# DRV8301.net
KiCad netlist of a schematic drawn in Altium Designer
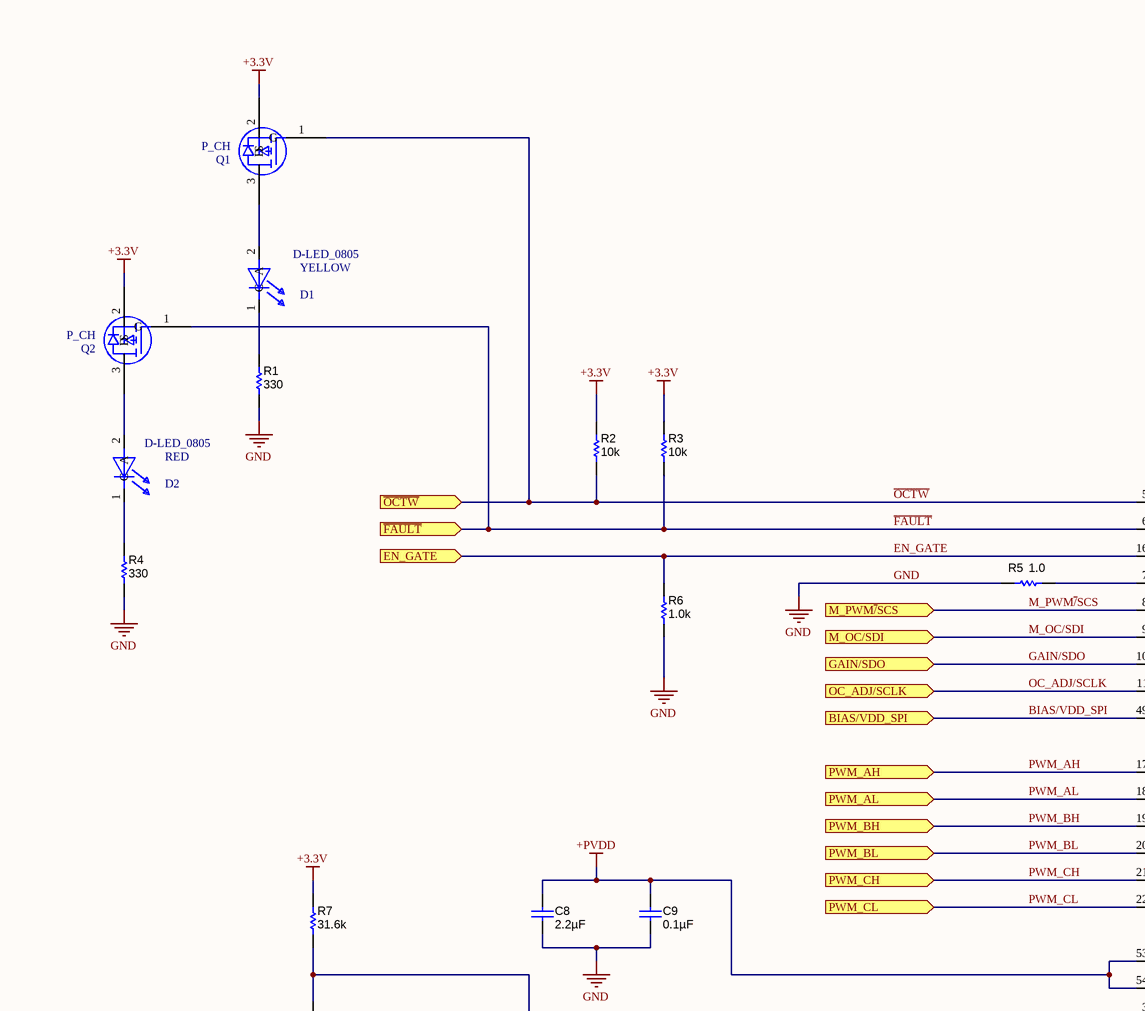
[diagram p0: DRV8301.SchDoc, top left]
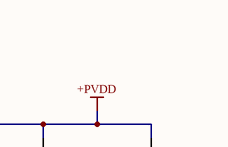
[diagram p1: DRV8301.SchDoc, top right]
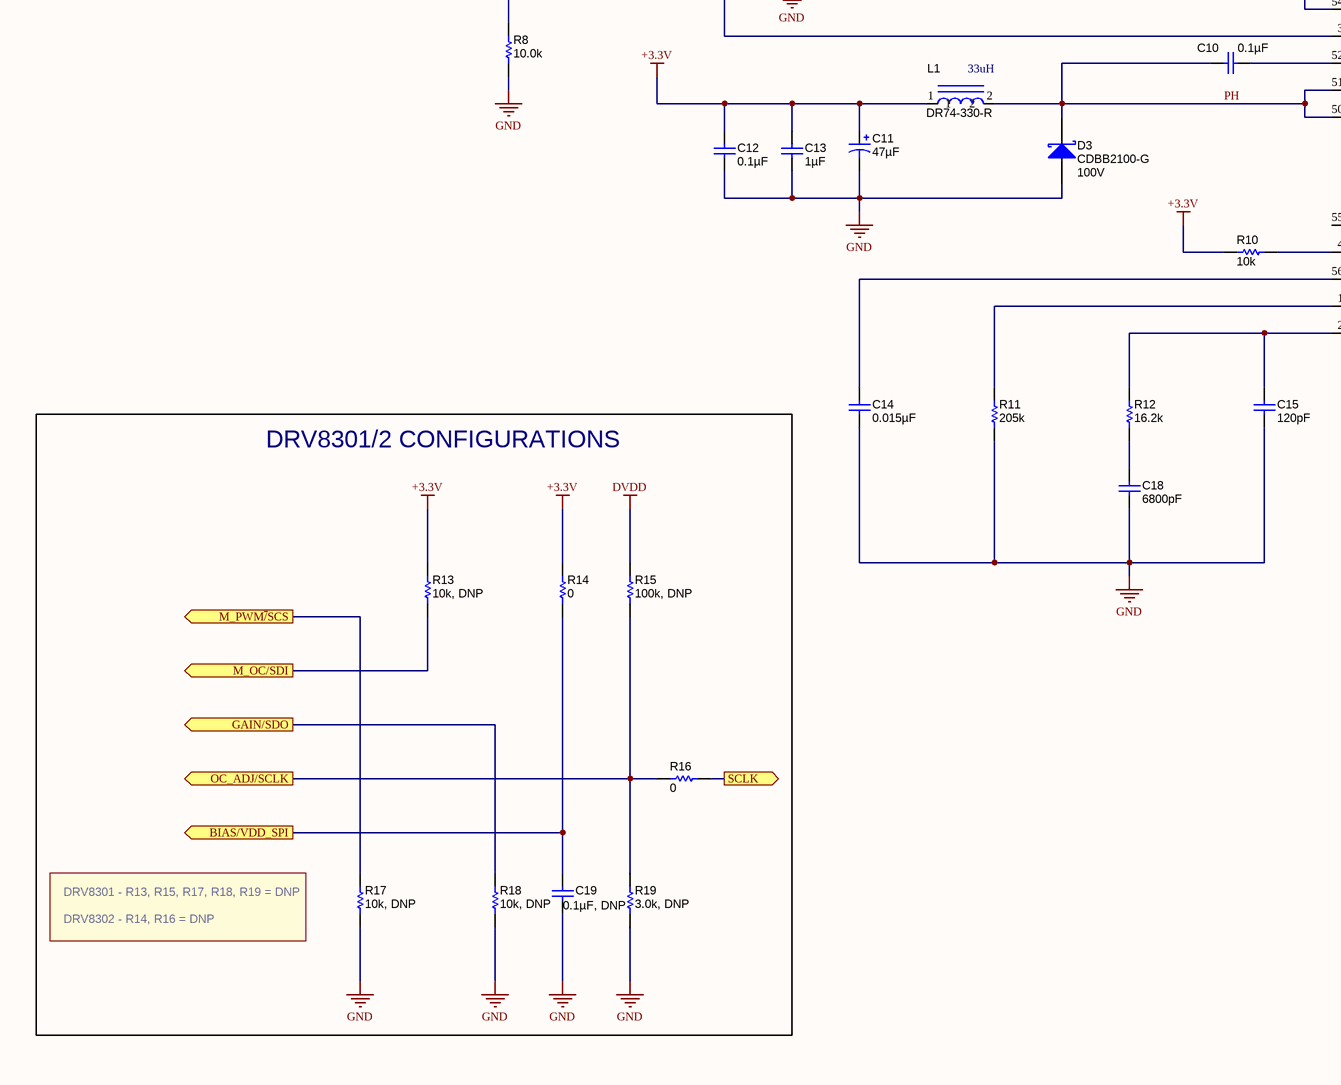
[diagram p2: DRV8301.SchDoc, bottom left]
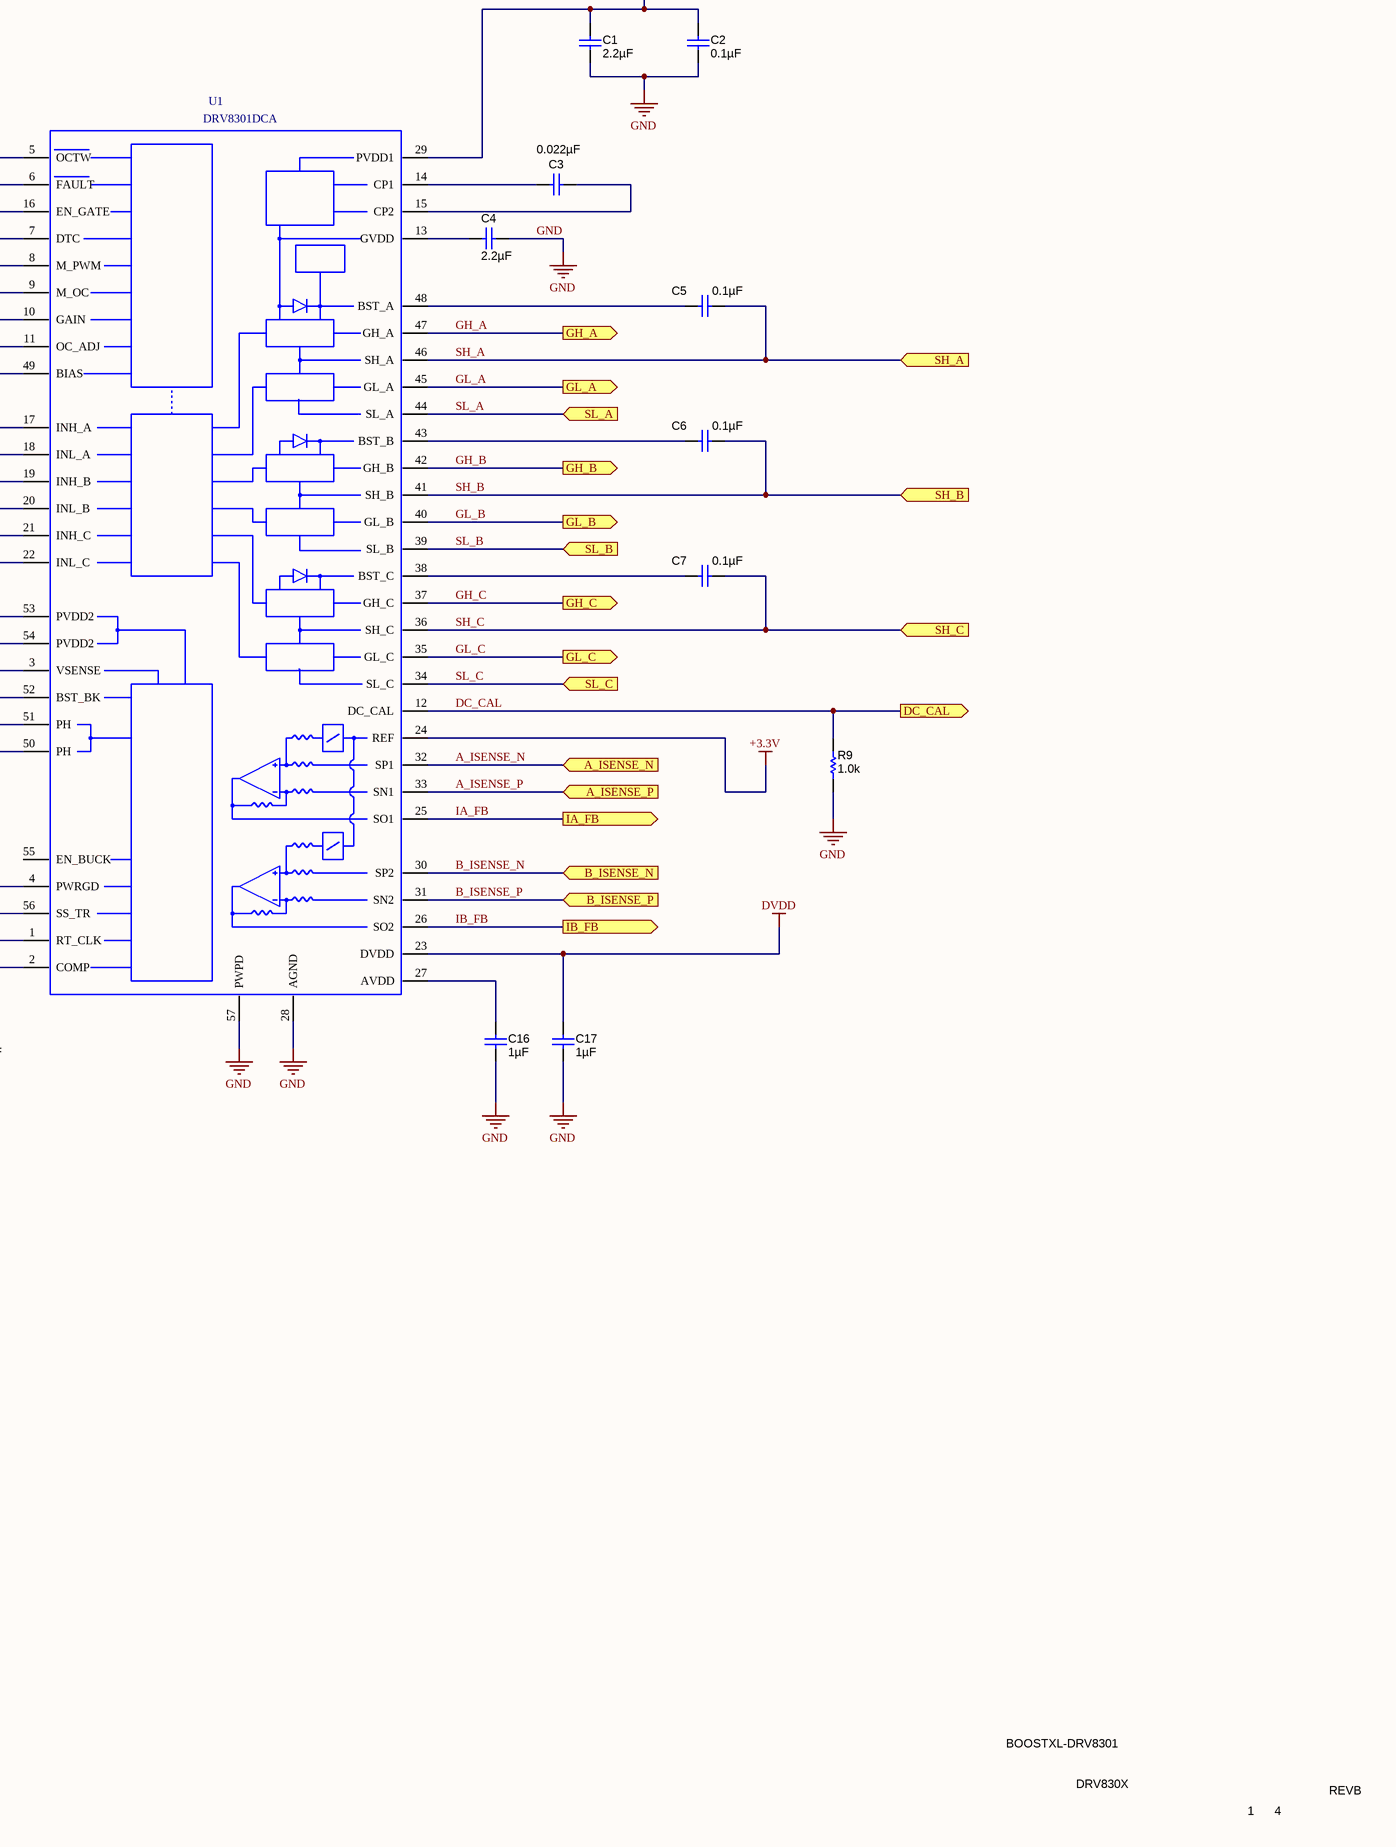
[diagram p3: DRV8301.SchDoc, bottom right]

(export (version "E")
  (design (tool "Eeschema 10.0.6"))
  (components
    (comp (ref "C1")
      (value "GRM32ER72A225KA35L")
      (footprint "1210L")
      (description "CAP, CERM, 2.2uF, 100V, +/-10%, X7R, 1210")
      (fields
        (field (name "VALUEDISPLAYED") "2.2µF")
        (field (name "MANUFACTURER") "MuRata")
        (field (name "PUBLISHER") "Texas Instruments")
      )
      (libsource (lib "Capacitor_Ceramic") (part "GRM32ER72A225KA35L"))
    )
    (comp (ref "C2")
      (value "GRM188R72A104KA35D")
      (footprint "0603L")
      (description "CAP, CERM, 0.1uF, 100V, +/-10%, X7R, 0603")
      (fields
        (field (name "VALUEDISPLAYED") "0.1µF")
        (field (name "MANUFACTURER") "MuRata")
        (field (name "PUBLISHER") "Texas Instruments")
      )
      (libsource (lib "Capacitor_Ceramic") (part "GRM188R72A104KA35D"))
    )
    (comp (ref "C3")
      (value "C1608X7R1H223K")
      (footprint "0603L")
      (description "CAP, CERM, 0.022uF, 50V, +/-10%, X7R, 0603")
      (fields
        (field (name "VALUEDISPLAYED") "0.022µF")
        (field (name "MANUFACTURER") "TDK")
        (field (name "PUBLISHER") "Texas Instruments")
      )
      (libsource (lib "Capacitor_Ceramic") (part "C1608X7R1H223K"))
    )
    (comp (ref "C4")
      (value "GRM219R61E225KA12D")
      (footprint "0805L")
      (description "CAP, CERM, 2.2uF, 25V, +/-10%, X5R, 0805")
      (fields
        (field (name "VALUEDISPLAYED") "2.2µF")
        (field (name "MANUFACTURER") "MuRata")
        (field (name "PUBLISHER") "Texas Instruments")
      )
      (libsource (lib "Capacitor_Ceramic") (part "GRM219R61E225KA12D"))
    )
    (comp (ref "C5")
      (value "C1608X7R1H104K")
      (footprint "0603L")
      (description "CAP, CERM, 0.1uF, 50V, +/-10%, X7R, 0603")
      (fields
        (field (name "VALUEDISPLAYED") "0.1µF")
        (field (name "MANUFACTURER") "TDK")
        (field (name "PUBLISHER") "Texas Instruments")
      )
      (libsource (lib "Capacitor_Ceramic") (part "C1608X7R1H104K"))
    )
    (comp (ref "C6")
      (value "C1608X7R1H104K")
      (footprint "0603L")
      (description "CAP, CERM, 0.1uF, 50V, +/-10%, X7R, 0603")
      (fields
        (field (name "VALUEDISPLAYED") "0.1µF")
        (field (name "MANUFACTURER") "TDK")
        (field (name "PUBLISHER") "Texas Instruments")
      )
      (libsource (lib "Capacitor_Ceramic") (part "C1608X7R1H104K"))
    )
    (comp (ref "C7")
      (value "C1608X7R1H104K")
      (footprint "0603L")
      (description "CAP, CERM, 0.1uF, 50V, +/-10%, X7R, 0603")
      (fields
        (field (name "VALUEDISPLAYED") "0.1µF")
        (field (name "MANUFACTURER") "TDK")
        (field (name "PUBLISHER") "Texas Instruments")
      )
      (libsource (lib "Capacitor_Ceramic") (part "C1608X7R1H104K"))
    )
    (comp (ref "C8")
      (value "GRM32ER72A225KA35L")
      (footprint "1210L")
      (description "CAP, CERM, 2.2uF, 100V, +/-10%, X7R, 1210")
      (fields
        (field (name "VALUEDISPLAYED") "2.2µF")
        (field (name "MANUFACTURER") "MuRata")
        (field (name "PUBLISHER") "Texas Instruments")
      )
      (libsource (lib "Capacitor_Ceramic") (part "GRM32ER72A225KA35L"))
    )
    (comp (ref "C9")
      (value "GRM188R72A104KA35D")
      (footprint "0603L")
      (description "CAP, CERM, 0.1uF, 100V, +/-10%, X7R, 0603")
      (fields
        (field (name "VALUEDISPLAYED") "0.1µF")
        (field (name "MANUFACTURER") "MuRata")
        (field (name "PUBLISHER") "Texas Instruments")
      )
      (libsource (lib "Capacitor_Ceramic") (part "GRM188R72A104KA35D"))
    )
    (comp (ref "C10")
      (value "C1608X7R1H104K")
      (footprint "0603L")
      (description "CAP, CERM, 0.1uF, 50V, +/-10%, X7R, 0603")
      (fields
        (field (name "VALUEDISPLAYED") "0.1µF")
        (field (name "MANUFACTURER") "TDK")
        (field (name "PUBLISHER") "Texas Instruments")
      )
      (libsource (lib "Capacitor_Ceramic") (part "C1608X7R1H104K"))
    )
    (comp (ref "C11")
      (value "EEE-FK1E470P")
      (footprint "SM_RADIAL_D")
      (description "CAP, AL, 47uF, 25V, +/-20%, 0.36 ohm, SMD")
      (fields
        (field (name "VALUEDISPLAYED") "47µF")
        (field (name "MANUFACTURER") "Panasonic")
        (field (name "PUBLISHER") "Texas Instruments")
      )
      (libsource (lib "Capacitor_Aluminum") (part "EEE-FK1E470P"))
    )
    (comp (ref "C12")
      (value "C1608X7R1E104K")
      (footprint "0603L")
      (description "CAP, CERM, 0.1uF, 25V, +/-10%, X7R, 0603")
      (fields
        (field (name "VALUEDISPLAYED") "0.1µF")
        (field (name "MANUFACTURER") "TDK")
        (field (name "PUBLISHER") "Texas Instruments")
      )
      (libsource (lib "Capacitor_Ceramic") (part "C1608X7R1E104K"))
    )
    (comp (ref "C13")
      (value "C1608X5R1E105K080AC")
      (footprint "0603L")
      (description "CAP, CERM, 1uF, 25V, +/-10%, X5R, 0603")
      (fields
        (field (name "VALUEDISPLAYED") "1µF")
        (field (name "MANUFACTURER") "TDK")
        (field (name "PUBLISHER") "Texas Instruments")
      )
      (libsource (lib "Capacitor_Ceramic") (part "C1608X5R1E105K080AC"))
    )
    (comp (ref "C14")
      (value "GRM188R71H153KA01D")
      (footprint "0603L")
      (description "CAP, CERM, 0.015uF, 50V, +/-10%, X7R, 0603")
      (fields
        (field (name "VALUEDISPLAYED") "0.015µF")
        (field (name "MANUFACTURER") "MuRata")
        (field (name "PUBLISHER") "Texas Instruments")
      )
      (libsource (lib "Capacitor_Ceramic") (part "GRM188R71H153KA01D"))
    )
    (comp (ref "C15")
      (value "GRM1885C1H121JA01D")
      (footprint "0603L")
      (description "CAP, CERM, 120pF, 50V, +/-5%, C0G/NP0, 0603")
      (fields
        (field (name "VALUEDISPLAYED") "120pF")
        (field (name "MANUFACTURER") "MuRata")
        (field (name "PUBLISHER") "Texas Instruments")
      )
      (libsource (lib "Capacitor_Ceramic") (part "GRM1885C1H121JA01D"))
    )
    (comp (ref "C16")
      (value "GRM188R61E105KA12D")
      (footprint "0603L")
      (description "CAP, CERM, 1uF, 25V, +/-10%, X5R, 0603")
      (fields
        (field (name "VALUEDISPLAYED") "1µF")
        (field (name "MANUFACTURER") "MuRata")
        (field (name "PUBLISHER") "Texas Instruments")
      )
      (libsource (lib "Capacitor_Ceramic") (part "GRM188R61E105KA12D"))
    )
    (comp (ref "C17")
      (value "GRM188R61E105KA12D")
      (footprint "0603L")
      (description "CAP, CERM, 1uF, 25V, +/-10%, X5R, 0603")
      (fields
        (field (name "VALUEDISPLAYED") "1µF")
        (field (name "MANUFACTURER") "MuRata")
        (field (name "PUBLISHER") "Texas Instruments")
      )
      (libsource (lib "Capacitor_Ceramic") (part "GRM188R61E105KA12D"))
    )
    (comp (ref "C18")
      (value "GRM188R71H682KA01D")
      (footprint "0603L")
      (description "CAP, CERM, 6800pF, 50V, +/-10%, X7R, 0603")
      (fields
        (field (name "VALUEDISPLAYED") "6800pF")
        (field (name "MANUFACTURER") "MuRata")
        (field (name "PUBLISHER") "Texas Instruments")
      )
      (libsource (lib "Capacitor_Ceramic") (part "GRM188R71H682KA01D"))
    )
    (comp (ref "C19")
      (value "C1608X7R1E104K")
      (footprint "0603L")
      (description "CAP, CERM, 0.1uF, 25V, +/-10%, X7R, 0603")
      (fields
        (field (name "VALUEDISPLAYED") "0.1µF, DNP")
        (field (name "MANUFACTURER") "TDK")
        (field (name "PUBLISHER") "Texas Instruments")
      )
      (libsource (lib "Capacitor_Ceramic") (part "C1608X7R1E104K"))
    )
    (comp (ref "D1")
      (value "D-LED_0805")
      (footprint "LED_0805")
      (description "LED THIN 585NM YEL DIFF 0805 SMD")
      (fields
        (field (name "PARTNUMBER") "SML-LXT0805YW-TR")
        (field (name "ALTIUM_VALUE") "YELLOW")
        (field (name "MANUFACTURER") "Lumex Opto/Components Inc")
      )
      (libsource (lib "*") (part "D-LED_0805"))
    )
    (comp (ref "D2")
      (value "D-LED_0805")
      (footprint "LED_0805")
      (description "LED THIN660NM SUPRED DIFF0805SMD")
      (fields
        (field (name "PARTNUMBER") "SML-LXT0805SRW-TR")
        (field (name "ALTIUM_VALUE") "RED")
        (field (name "MANUFACTURER") "Lumex Opto/Components Inc")
      )
      (libsource (lib "*") (part "D-LED_0805"))
    )
    (comp (ref "D3")
      (value "CDBB2100-G")
      (footprint "SMB")
      (description "Diode, Schottky, 100V, 2A, SMB")
      (fields
        (field (name "ALTIUM_VALUE") "100V")
        (field (name "MANUFACTURER") "Comchip Technology")
        (field (name "PUBLISHER") "Texas Instruments")
      )
      (libsource (lib "Diode") (part "CDBC5100-G"))
    )
    (comp (ref "L1")
      (value "DR74-330-R")
      (footprint "IND_DR74")
      (description "INDUCTOR SHIELD PWR 33UH SMD")
      (fields (field (name "MANUFACTURER") "Cooper Bussmann") (field (name "ALTIUM_VALUE") "33uH"))
      (libsource (lib "PADSlegacy_Passive") (part "IND_DR74-XXX"))
    )
    (comp (ref "Q1")
      (value "P_CH")
      (footprint "SOT-23")
      (description "MOSFET P-CH 8V 5.4A SOT23-3")
      (fields (field (name "PARTNUMBER") "SI2325DS-T1-E3") (field (name "MANUFACTURER") "Vishey Siliconix"))
      (libsource (lib "*") (part "TR_PFET_SOT23"))
    )
    (comp (ref "Q2")
      (value "P_CH")
      (footprint "SOT-23")
      (description "MOSFET P-CH 8V 5.4A SOT23-3")
      (fields (field (name "PARTNUMBER") "SI2325DS-T1-E3") (field (name "MANUFACTURER") "Vishey Siliconix"))
      (libsource (lib "*") (part "TR_PFET_SOT23"))
    )
    (comp (ref "R1")
      (value "330")
      (footprint "0603L")
      (description "RES, 330 ohm, 5%, 0.1W, 0603")
      (fields
        (field (name "PARTNUMBER") "CRCW0603330RJNEA")
        (field (name "MANUFACTURER") "Vishay-Dale")
        (field (name "PUBLISHER") "Texas Instruments")
      )
      (libsource (lib "Resistor_0603") (part "CRCW0603330RJNEA"))
    )
    (comp (ref "R2")
      (value "10k")
      (footprint "0603L")
      (description "RES, 10k ohm, 5%, 0.1W, 0603")
      (fields
        (field (name "PARTNUMBER") "CRCW060310K0JNEA")
        (field (name "MANUFACTURER") "Vishay-Dale")
        (field (name "PUBLISHER") "Texas Instruments")
      )
      (libsource (lib "Resistor_0603") (part "CRCW060310K0JNEA"))
    )
    (comp (ref "R3")
      (value "10k")
      (footprint "0603L")
      (description "RES, 10k ohm, 5%, 0.1W, 0603")
      (fields
        (field (name "PARTNUMBER") "CRCW060310K0JNEA")
        (field (name "MANUFACTURER") "Vishay-Dale")
        (field (name "PUBLISHER") "Texas Instruments")
      )
      (libsource (lib "Resistor_0603") (part "CRCW060310K0JNEA"))
    )
    (comp (ref "R4")
      (value "330")
      (footprint "0603L")
      (description "RES, 330 ohm, 5%, 0.1W, 0603")
      (fields
        (field (name "PARTNUMBER") "CRCW0603330RJNEA")
        (field (name "MANUFACTURER") "Vishay-Dale")
        (field (name "PUBLISHER") "Texas Instruments")
      )
      (libsource (lib "Resistor_0603") (part "CRCW0603330RJNEA"))
    )
    (comp (ref "R5")
      (value "1.0")
      (footprint "0603L")
      (description "RES, 1.0 ohm, 5%, 0.1W, 0603")
      (fields
        (field (name "PARTNUMBER") "CRCW06031R00JNEA")
        (field (name "MANUFACTURER") "Vishay-Dale")
        (field (name "PUBLISHER") "Texas Instruments")
      )
      (libsource (lib "Resistor_0603") (part "CRCW06031R00JNEA"))
    )
    (comp (ref "R6")
      (value "1.0k")
      (footprint "0603L")
      (description "RES, 1.0k ohm, 5%, 0.1W, 0603")
      (fields
        (field (name "PARTNUMBER") "CRCW06031K00JNEA")
        (field (name "MANUFACTURER") "Vishay-Dale")
        (field (name "PUBLISHER") "Texas Instruments")
      )
      (libsource (lib "Resistor_0603") (part "CRCW06031K00JNEA"))
    )
    (comp (ref "R7")
      (value "31.6k")
      (footprint "0603L")
      (description "RES, 31.6k ohm, 1%, 0.1W, 0603")
      (fields
        (field (name "PARTNUMBER") "CRCW060331K6FKEA")
        (field (name "MANUFACTURER") "Vishay-Dale")
        (field (name "PUBLISHER") "Texas Instruments")
      )
      (libsource (lib "Resistor_0603") (part "CRCW060331K6FKEA"))
    )
    (comp (ref "R8")
      (value "10.0k")
      (footprint "0603L")
      (description "RES, 10.0k ohm, 0.1%, 0.1W, 0603")
      (fields
        (field (name "PARTNUMBER") "RG1608P-103-B-T5")
        (field (name "MANUFACTURER") "Susumu Co Ltd")
        (field (name "PUBLISHER") "Texas Instruments")
      )
      (libsource (lib "Resistor_0603") (part "RG1608P-103-B-T5"))
    )
    (comp (ref "R9")
      (value "1.0k")
      (footprint "0603L")
      (description "RES, 1.0k ohm, 5%, 0.1W, 0603")
      (fields
        (field (name "PARTNUMBER") "CRCW06031K00JNEA")
        (field (name "MANUFACTURER") "Vishay-Dale")
        (field (name "PUBLISHER") "Texas Instruments")
      )
      (libsource (lib "Resistor_0603") (part "CRCW06031K00JNEA"))
    )
    (comp (ref "R10")
      (value "10k")
      (footprint "0603L")
      (description "RES, 10k ohm, 5%, 0.1W, 0603")
      (fields
        (field (name "PARTNUMBER") "CRCW060310K0JNEA")
        (field (name "MANUFACTURER") "Vishay-Dale")
        (field (name "PUBLISHER") "Texas Instruments")
      )
      (libsource (lib "Resistor_0603") (part "CRCW060310K0JNEA"))
    )
    (comp (ref "R11")
      (value "205k")
      (footprint "0603L")
      (description "RES, 205k ohm, 1%, 0.1W, 0603")
      (fields
        (field (name "PARTNUMBER") "CRCW0603205KFKEA")
        (field (name "MANUFACTURER") "Vishay-Dale")
        (field (name "PUBLISHER") "Texas Instruments")
      )
      (libsource (lib "Resistor_0603") (part "CRCW0603205KFKEA"))
    )
    (comp (ref "R12")
      (value "16.2k")
      (footprint "0603L")
      (description "RES, 16.2k ohm, 1%, 0.1W, 0603")
      (fields
        (field (name "PARTNUMBER") "CRCW060316K2FKEA")
        (field (name "MANUFACTURER") "Vishay-Dale")
        (field (name "PUBLISHER") "Texas Instruments")
      )
      (libsource (lib "Resistor_0603") (part "CRCW060316K2FKEA"))
    )
    (comp (ref "R13")
      (value "10k, DNP")
      (footprint "0603L")
      (description "RES, 10k ohm, 5%, 0.1W, 0603")
      (fields
        (field (name "PARTNUMBER") "CRCW060310K0JNEA")
        (field (name "MANUFACTURER") "Vishay-Dale")
        (field (name "PUBLISHER") "Texas Instruments")
      )
      (libsource (lib "Resistor_0603") (part "CRCW060310K0JNEA"))
    )
    (comp (ref "R14")
      (value "0")
      (footprint "0603L")
      (description "RES, 0 ohm, 5%, 0.1W, 0603")
      (fields
        (field (name "PARTNUMBER") "CRCW06030000Z0EA")
        (field (name "MANUFACTURER") "Vishay-Dale")
        (field (name "PUBLISHER") "Texas Instruments")
      )
      (libsource (lib "Resistor_0603") (part "CRCW06030000Z0EA"))
    )
    (comp (ref "R15")
      (value "100k, DNP")
      (footprint "0603L")
      (description "RES, 100k ohm, 5%, 0.1W, 0603")
      (fields
        (field (name "PARTNUMBER") "CRCW0603100KJNEA")
        (field (name "MANUFACTURER") "Vishay-Dale")
        (field (name "PUBLISHER") "Texas Instruments")
      )
      (libsource (lib "Resistor_0603") (part "CRCW0603100KJNEA"))
    )
    (comp (ref "R16")
      (value "0")
      (footprint "0603L")
      (description "RES, 0 ohm, 5%, 0.1W, 0603")
      (fields
        (field (name "PARTNUMBER") "CRCW06030000Z0EA")
        (field (name "MANUFACTURER") "Vishay-Dale")
        (field (name "PUBLISHER") "Texas Instruments")
      )
      (libsource (lib "Resistor_0603") (part "CRCW06030000Z0EA"))
    )
    (comp (ref "R17")
      (value "10k, DNP")
      (footprint "0603L")
      (description "RES, 10k ohm, 5%, 0.1W, 0603")
      (fields
        (field (name "PARTNUMBER") "CRCW060310K0JNEA")
        (field (name "MANUFACTURER") "Vishay-Dale")
        (field (name "PUBLISHER") "Texas Instruments")
      )
      (libsource (lib "Resistor_0603") (part "CRCW060310K0JNEA"))
    )
    (comp (ref "R18")
      (value "10k, DNP")
      (footprint "0603L")
      (description "RES, 10k ohm, 5%, 0.1W, 0603")
      (fields
        (field (name "PARTNUMBER") "CRCW060310K0JNEA")
        (field (name "MANUFACTURER") "Vishay-Dale")
        (field (name "PUBLISHER") "Texas Instruments")
      )
      (libsource (lib "Resistor_0603") (part "CRCW060310K0JNEA"))
    )
    (comp (ref "R19")
      (value "3.0k, DNP")
      (footprint "0603L")
      (description "RES, 3.0k ohm, 5%, 0.1W, 0603")
      (fields
        (field (name "PARTNUMBER") "CRCW06033K00JNEA")
        (field (name "MANUFACTURER") "Vishay-Dale")
        (field (name "PUBLISHER") "Texas Instruments")
      )
      (libsource (lib "Resistor_0603") (part "CRCW06033K00JNEA"))
    )
    (comp (ref "U1")
      (value "DRV8301DCA")
      (footprint "DCA_56P")
      (description "IC, 3 Phase Pre-Driver with Dual Current Shunt Amplifiers and Buck Regulator-Hardware Controlled")
      (fields (field (name "MANUFACTURER") "Texas Instruments") (field (name "VENDOR PART #") "Supplied"))
      (libsource (lib "*") (part "DRV8302DCA_ERIC"))
    )
  )
  (nets
    (net (code "1") (name "+3.3V") (class "Default")
      (node (ref "C11") (pin "1") (pinfunction "+_1") (pintype "passive"))
      (node (ref "C12") (pin "1") (pinfunction "1_1") (pintype "passive"))
      (node (ref "C13") (pin "1") (pinfunction "1_1") (pintype "passive"))
      (node (ref "L1") (pin "1") (pinfunction "1_1") (pintype "passive"))
      (node (ref "Q1") (pin "2") (pinfunction "S_2") (pintype "passive"))
      (node (ref "Q2") (pin "2") (pinfunction "S_2") (pintype "passive"))
      (node (ref "R10") (pin "2") (pinfunction "2_2") (pintype "passive"))
      (node (ref "R13") (pin "2") (pinfunction "2_2") (pintype "passive"))
      (node (ref "R14") (pin "2") (pinfunction "2_2") (pintype "passive"))
      (node (ref "R2") (pin "2") (pinfunction "2_2") (pintype "passive"))
      (node (ref "R3") (pin "2") (pinfunction "2_2") (pintype "passive"))
      (node (ref "R7") (pin "2") (pinfunction "2_2") (pintype "passive"))
      (node (ref "U1") (pin "24") (pinfunction "REF_24") (pintype "passive"))
    )
    (net (code "2") (name "+PVDD") (class "Default")
      (node (ref "C1") (pin "1") (pinfunction "1_1") (pintype "passive"))
      (node (ref "C2") (pin "1") (pinfunction "1_1") (pintype "passive"))
      (node (ref "C8") (pin "1") (pinfunction "1_1") (pintype "passive"))
      (node (ref "C9") (pin "1") (pinfunction "1_1") (pintype "passive"))
      (node (ref "U1") (pin "29") (pinfunction "PVDD1_29") (pintype "passive"))
      (node (ref "U1") (pin "53") (pinfunction "PVDD2_53") (pintype "passive"))
      (node (ref "U1") (pin "54") (pinfunction "PVDD2_54") (pintype "passive"))
    )
    (net (code "3") (name "/A_ISENSE_N") (class "Default")
      (node (ref "U1") (pin "32") (pinfunction "SP1_32") (pintype "passive"))
    )
    (net (code "4") (name "/A_ISENSE_P") (class "Default")
      (node (ref "U1") (pin "33") (pinfunction "SN1_33") (pintype "passive"))
    )
    (net (code "5") (name "/BIAS{slash}VDD_SPI") (class "Default")
      (node (ref "C19") (pin "1") (pinfunction "1_1") (pintype "passive"))
      (node (ref "R14") (pin "1") (pinfunction "1_1") (pintype "passive"))
      (node (ref "U1") (pin "49") (pinfunction "BIAS_49") (pintype "passive"))
    )
    (net (code "6") (name "/B_ISENSE_N") (class "Default")
      (node (ref "U1") (pin "30") (pinfunction "SP2_30") (pintype "passive"))
    )
    (net (code "7") (name "/B_ISENSE_P") (class "Default")
      (node (ref "U1") (pin "31") (pinfunction "SN2_31") (pintype "passive"))
    )
    (net (code "8") (name "/DC_CAL") (class "Default")
      (node (ref "R9") (pin "2") (pinfunction "2_2") (pintype "passive"))
      (node (ref "U1") (pin "12") (pinfunction "DC_CAL_12") (pintype "passive"))
    )
    (net (code "9") (name "/EN_GATE") (class "Default")
      (node (ref "R6") (pin "2") (pinfunction "2_2") (pintype "passive"))
      (node (ref "U1") (pin "16") (pinfunction "EN_GATE_16") (pintype "passive"))
    )
    (net (code "10") (name "/FAULT") (class "Default")
      (node (ref "Q2") (pin "1") (pinfunction "G_1") (pintype "passive"))
      (node (ref "R3") (pin "1") (pinfunction "1_1") (pintype "passive"))
      (node (ref "U1") (pin "6") (pinfunction "FAULT_6") (pintype "passive"))
    )
    (net (code "11") (name "/GAIN{slash}SDO") (class "Default")
      (node (ref "R18") (pin "2") (pinfunction "2_2") (pintype "passive"))
      (node (ref "U1") (pin "10") (pinfunction "GAIN_10") (pintype "passive"))
    )
    (net (code "12") (name "/GH_A") (class "Default")
      (node (ref "U1") (pin "47") (pinfunction "GH_A_47") (pintype "passive"))
    )
    (net (code "13") (name "/GH_B") (class "Default")
      (node (ref "U1") (pin "42") (pinfunction "GH_B_42") (pintype "passive"))
    )
    (net (code "14") (name "/GH_C") (class "Default")
      (node (ref "U1") (pin "37") (pinfunction "GH_C_37") (pintype "passive"))
    )
    (net (code "15") (name "/GL_A") (class "Default")
      (node (ref "U1") (pin "45") (pinfunction "GL_A_45") (pintype "passive"))
    )
    (net (code "16") (name "/GL_B") (class "Default")
      (node (ref "U1") (pin "40") (pinfunction "GL_B_40") (pintype "passive"))
    )
    (net (code "17") (name "/GL_C") (class "Default")
      (node (ref "U1") (pin "35") (pinfunction "GL_C_35") (pintype "passive"))
    )
    (net (code "18") (name "/IA_FB") (class "Default")
      (node (ref "U1") (pin "25") (pinfunction "SO1_25") (pintype "passive"))
    )
    (net (code "19") (name "/IB_FB") (class "Default")
      (node (ref "U1") (pin "26") (pinfunction "SO2_26") (pintype "passive"))
    )
    (net (code "20") (name "/M_OC{slash}SDI") (class "Default")
      (node (ref "R13") (pin "1") (pinfunction "1_1") (pintype "passive"))
      (node (ref "U1") (pin "9") (pinfunction "M_OC_9") (pintype "passive"))
    )
    (net (code "21") (name "/M_PWM~{{slash}}SCS") (class "Default")
      (node (ref "R17") (pin "2") (pinfunction "2_2") (pintype "passive"))
      (node (ref "U1") (pin "8") (pinfunction "M_PWM_8") (pintype "passive"))
    )
    (net (code "22") (name "/OCTW") (class "Default")
      (node (ref "Q1") (pin "1") (pinfunction "G_1") (pintype "passive"))
      (node (ref "R2") (pin "1") (pinfunction "1_1") (pintype "passive"))
      (node (ref "U1") (pin "5") (pinfunction "OCTW_5") (pintype "passive"))
    )
    (net (code "23") (name "/OC_ADJ{slash}SCLK") (class "Default")
      (node (ref "R15") (pin "2") (pinfunction "2_2") (pintype "passive"))
      (node (ref "R16") (pin "2") (pinfunction "2_2") (pintype "passive"))
      (node (ref "R19") (pin "2") (pinfunction "2_2") (pintype "passive"))
      (node (ref "U1") (pin "11") (pinfunction "OC_ADJ_11") (pintype "passive"))
    )
    (net (code "24") (name "/PH") (class "Default")
      (node (ref "C10") (pin "1") (pinfunction "1_1") (pintype "passive"))
      (node (ref "D3") (pin "1") (pinfunction "K_1") (pintype "passive"))
      (node (ref "L1") (pin "2") (pinfunction "2_2") (pintype "passive"))
      (node (ref "U1") (pin "50") (pinfunction "PH_50") (pintype "passive"))
      (node (ref "U1") (pin "51") (pinfunction "PH_51") (pintype "passive"))
    )
    (net (code "25") (name "/PWM_AH") (class "Default")
      (node (ref "U1") (pin "17") (pinfunction "INH_A_17") (pintype "passive"))
    )
    (net (code "26") (name "/PWM_AL") (class "Default")
      (node (ref "U1") (pin "18") (pinfunction "INL_A_18") (pintype "passive"))
    )
    (net (code "27") (name "/PWM_BH") (class "Default")
      (node (ref "U1") (pin "19") (pinfunction "INH_B_19") (pintype "passive"))
    )
    (net (code "28") (name "/PWM_BL") (class "Default")
      (node (ref "U1") (pin "20") (pinfunction "INL_B_20") (pintype "passive"))
    )
    (net (code "29") (name "/PWM_CH") (class "Default")
      (node (ref "U1") (pin "21") (pinfunction "INH_C_21") (pintype "passive"))
    )
    (net (code "30") (name "/PWM_CL") (class "Default")
      (node (ref "U1") (pin "22") (pinfunction "INL_C_22") (pintype "passive"))
    )
    (net (code "31") (name "/SCLK") (class "Default")
      (node (ref "R16") (pin "1") (pinfunction "1_1") (pintype "passive"))
    )
    (net (code "32") (name "/SH_A") (class "Default")
      (node (ref "C5") (pin "2") (pinfunction "2_2") (pintype "passive"))
      (node (ref "U1") (pin "46") (pinfunction "SH_A_46") (pintype "passive"))
    )
    (net (code "33") (name "/SH_B") (class "Default")
      (node (ref "C6") (pin "2") (pinfunction "2_2") (pintype "passive"))
      (node (ref "U1") (pin "41") (pinfunction "SH_B_41") (pintype "passive"))
    )
    (net (code "34") (name "/SH_C") (class "Default")
      (node (ref "C7") (pin "2") (pinfunction "2_2") (pintype "passive"))
      (node (ref "U1") (pin "36") (pinfunction "SH_C_36") (pintype "passive"))
    )
    (net (code "35") (name "/SL_A") (class "Default")
      (node (ref "U1") (pin "44") (pinfunction "SL_A_44") (pintype "passive"))
    )
    (net (code "36") (name "/SL_B") (class "Default")
      (node (ref "U1") (pin "39") (pinfunction "SL_B_39") (pintype "passive"))
    )
    (net (code "37") (name "/SL_C") (class "Default")
      (node (ref "U1") (pin "34") (pinfunction "SL_C_34") (pintype "passive"))
    )
    (net (code "38") (name "DVDD") (class "Default")
      (node (ref "C17") (pin "1") (pinfunction "1_1") (pintype "passive"))
      (node (ref "R15") (pin "1") (pinfunction "1_1") (pintype "passive"))
      (node (ref "U1") (pin "23") (pinfunction "DVDD_23") (pintype "passive"))
    )
    (net (code "39") (name "GND") (class "Default")
      (node (ref "C1") (pin "2") (pinfunction "2_2") (pintype "passive"))
      (node (ref "C11") (pin "2") (pinfunction "-_2") (pintype "passive"))
      (node (ref "C12") (pin "2") (pinfunction "2_2") (pintype "passive"))
      (node (ref "C13") (pin "2") (pinfunction "2_2") (pintype "passive"))
      (node (ref "C14") (pin "2") (pinfunction "2_2") (pintype "passive"))
      (node (ref "C15") (pin "2") (pinfunction "2_2") (pintype "passive"))
      (node (ref "C16") (pin "2") (pinfunction "2_2") (pintype "passive"))
      (node (ref "C17") (pin "2") (pinfunction "2_2") (pintype "passive"))
      (node (ref "C18") (pin "2") (pinfunction "2_2") (pintype "passive"))
      (node (ref "C19") (pin "2") (pinfunction "2_2") (pintype "passive"))
      (node (ref "C2") (pin "2") (pinfunction "2_2") (pintype "passive"))
      (node (ref "C4") (pin "2") (pinfunction "2_2") (pintype "passive"))
      (node (ref "C8") (pin "2") (pinfunction "2_2") (pintype "passive"))
      (node (ref "C9") (pin "2") (pinfunction "2_2") (pintype "passive"))
      (node (ref "D3") (pin "2") (pinfunction "A_2") (pintype "passive"))
      (node (ref "R1") (pin "1") (pinfunction "1_1") (pintype "passive"))
      (node (ref "R11") (pin "1") (pinfunction "1_1") (pintype "passive"))
      (node (ref "R17") (pin "1") (pinfunction "1_1") (pintype "passive"))
      (node (ref "R18") (pin "1") (pinfunction "1_1") (pintype "passive"))
      (node (ref "R19") (pin "1") (pinfunction "1_1") (pintype "passive"))
      (node (ref "R4") (pin "1") (pinfunction "1_1") (pintype "passive"))
      (node (ref "R5") (pin "1") (pinfunction "1_1") (pintype "passive"))
      (node (ref "R6") (pin "1") (pinfunction "1_1") (pintype "passive"))
      (node (ref "R8") (pin "1") (pinfunction "1_1") (pintype "passive"))
      (node (ref "R9") (pin "1") (pinfunction "1_1") (pintype "passive"))
      (node (ref "U1") (pin "28") (pinfunction "AGND_28") (pintype "passive"))
      (node (ref "U1") (pin "57") (pinfunction "PWPD_57") (pintype "passive"))
    )
    (net (code "40") (name "Net-(C18-Pad1)") (class "Default")
      (node (ref "C18") (pin "1") (pinfunction "1_1") (pintype "passive"))
      (node (ref "R12") (pin "1") (pinfunction "1_1") (pintype "passive"))
    )
    (net (code "41") (name "Net-(D1-A)") (class "Default")
      (node (ref "D1") (pin "2") (pinfunction "A_2") (pintype "passive"))
      (node (ref "Q1") (pin "3") (pinfunction "D_3") (pintype "passive"))
    )
    (net (code "42") (name "Net-(D1-C)") (class "Default")
      (node (ref "D1") (pin "1") (pinfunction "C_1") (pintype "passive"))
      (node (ref "R1") (pin "2") (pinfunction "2_2") (pintype "passive"))
    )
    (net (code "43") (name "Net-(D2-A)") (class "Default")
      (node (ref "D2") (pin "2") (pinfunction "A_2") (pintype "passive"))
      (node (ref "Q2") (pin "3") (pinfunction "D_3") (pintype "passive"))
    )
    (net (code "44") (name "Net-(D2-C)") (class "Default")
      (node (ref "D2") (pin "1") (pinfunction "C_1") (pintype "passive"))
      (node (ref "R4") (pin "2") (pinfunction "2_2") (pintype "passive"))
    )
    (net (code "45") (name "Net-(U1-AVDD)") (class "Default")
      (node (ref "C16") (pin "1") (pinfunction "1_1") (pintype "passive"))
      (node (ref "U1") (pin "27") (pinfunction "AVDD_27") (pintype "passive"))
    )
    (net (code "46") (name "Net-(U1-BST_A)") (class "Default")
      (node (ref "C5") (pin "1") (pinfunction "1_1") (pintype "passive"))
      (node (ref "U1") (pin "48") (pinfunction "BST_A_48") (pintype "passive"))
    )
    (net (code "47") (name "Net-(U1-BST_B)") (class "Default")
      (node (ref "C6") (pin "1") (pinfunction "1_1") (pintype "passive"))
      (node (ref "U1") (pin "43") (pinfunction "BST_B_43") (pintype "passive"))
    )
    (net (code "48") (name "Net-(U1-BST_BK)") (class "Default")
      (node (ref "C10") (pin "2") (pinfunction "2_2") (pintype "passive"))
      (node (ref "U1") (pin "52") (pinfunction "BST_BK_52") (pintype "passive"))
    )
    (net (code "49") (name "Net-(U1-BST_C)") (class "Default")
      (node (ref "C7") (pin "1") (pinfunction "1_1") (pintype "passive"))
      (node (ref "U1") (pin "38") (pinfunction "BST_C_38") (pintype "passive"))
    )
    (net (code "50") (name "Net-(U1-COMP)") (class "Default")
      (node (ref "C15") (pin "1") (pinfunction "1_1") (pintype "passive"))
      (node (ref "R12") (pin "2") (pinfunction "2_2") (pintype "passive"))
      (node (ref "U1") (pin "2") (pinfunction "COMP_2") (pintype "passive"))
    )
    (net (code "51") (name "Net-(U1-CP1)") (class "Default")
      (node (ref "C3") (pin "1") (pinfunction "1_1") (pintype "passive"))
      (node (ref "U1") (pin "14") (pinfunction "CP1_14") (pintype "passive"))
    )
    (net (code "52") (name "Net-(U1-CP2)") (class "Default")
      (node (ref "C3") (pin "2") (pinfunction "2_2") (pintype "passive"))
      (node (ref "U1") (pin "15") (pinfunction "CP2_15") (pintype "passive"))
    )
    (net (code "53") (name "Net-(U1-DTC)") (class "Default")
      (node (ref "R5") (pin "2") (pinfunction "2_2") (pintype "passive"))
      (node (ref "U1") (pin "7") (pinfunction "DTC_7") (pintype "passive"))
    )
    (net (code "54") (name "Net-(U1-GVDD)") (class "Default")
      (node (ref "C4") (pin "1") (pinfunction "1_1") (pintype "passive"))
      (node (ref "U1") (pin "13") (pinfunction "GVDD_13") (pintype "passive"))
    )
    (net (code "55") (name "Net-(U1-PWRGD)") (class "Default")
      (node (ref "R10") (pin "1") (pinfunction "1_1") (pintype "passive"))
      (node (ref "U1") (pin "4") (pinfunction "PWRGD_4") (pintype "passive"))
    )
    (net (code "56") (name "Net-(U1-RT_CLK)") (class "Default")
      (node (ref "R11") (pin "2") (pinfunction "2_2") (pintype "passive"))
      (node (ref "U1") (pin "1") (pinfunction "RT_CLK_1") (pintype "passive"))
    )
    (net (code "57") (name "Net-(U1-SS_TR)") (class "Default")
      (node (ref "C14") (pin "1") (pinfunction "1_1") (pintype "passive"))
      (node (ref "U1") (pin "56") (pinfunction "SS_TR_56") (pintype "passive"))
    )
    (net (code "58") (name "Net-(U1-VSENSE)") (class "Default")
      (node (ref "R7") (pin "1") (pinfunction "1_1") (pintype "passive"))
      (node (ref "R8") (pin "2") (pinfunction "2_2") (pintype "passive"))
      (node (ref "U1") (pin "3") (pinfunction "VSENSE_3") (pintype "passive"))
    )
    (net (code "59") (name "unconnected-(U1-EN_BUCK-Pad55)") (class "Default")
      (node (ref "U1") (pin "55") (pinfunction "EN_BUCK_55") (pintype "passive"))
    )
  )
)
